# 2_Connectors.net
KiCad netlist of a schematic drawn in Altium Designer
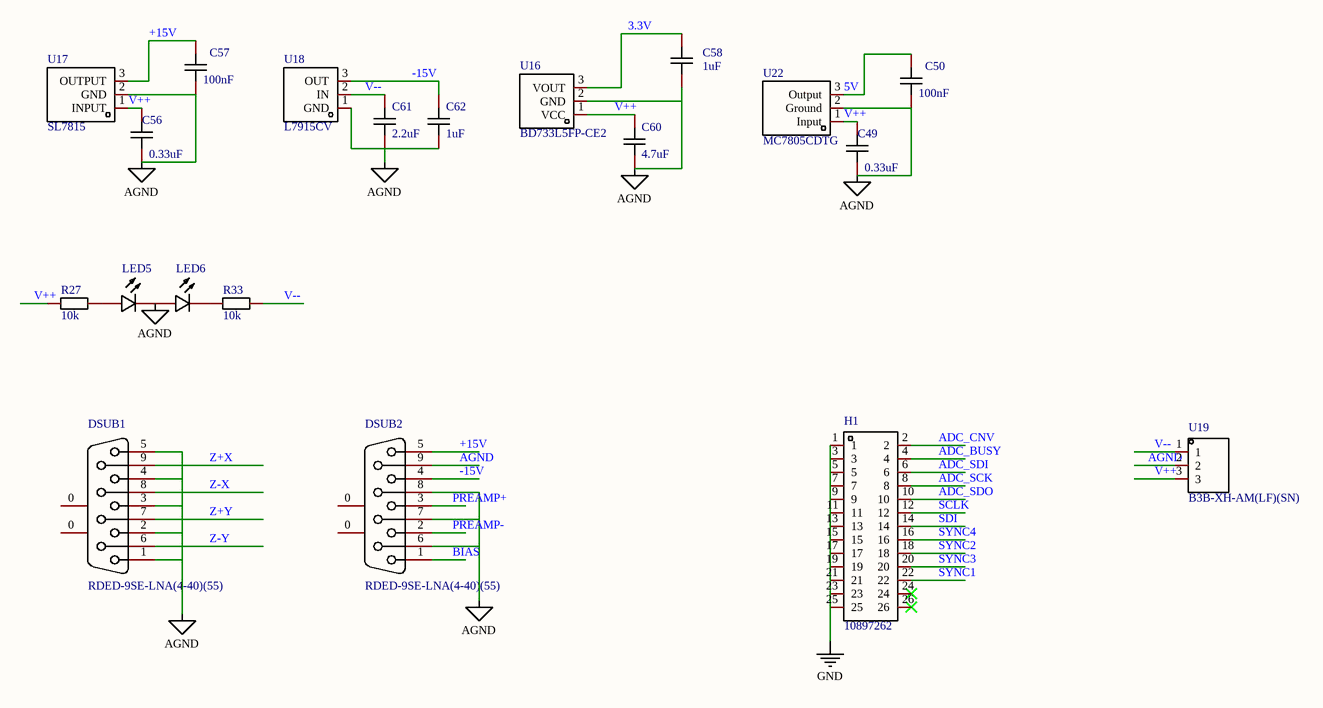
[diagram p0: 2_Connectors.schdoc]

(export (version "E")
  (design (tool "Eeschema 10.0.6"))
  (components
    (comp (ref "C49")
      (value "0.33uF")
      (fields (field (name "NAME") "0.33uF"))
      (libsource (lib "altium-import") (part "root_1_CAP_0603_"))
    )
    (comp (ref "C50")
      (value "100nF")
      (fields (field (name "NAME") "100nF"))
      (libsource (lib "altium-import") (part "root_3_CAP_0603_"))
    )
    (comp (ref "C56")
      (value "0.33uF")
      (fields (field (name "NAME") "0.33uF"))
      (libsource (lib "altium-import") (part "root_1_CAP_0603_"))
    )
    (comp (ref "C57")
      (value "100nF")
      (fields (field (name "NAME") "100nF"))
      (libsource (lib "altium-import") (part "root_3_CAP_0603_"))
    )
    (comp (ref "C58")
      (value "1uF")
      (fields (field (name "NAME") "1uF"))
      (libsource (lib "altium-import") (part "root_3_CAP_0603_"))
    )
    (comp (ref "C60")
      (value "4.7uF")
      (fields (field (name "NAME") "4.7uF"))
      (libsource (lib "altium-import") (part "root_1_CAP_0603_"))
    )
    (comp (ref "C61")
      (value "2.2uF")
      (fields (field (name "NAME") "2.2uF"))
      (libsource (lib "altium-import") (part "root_1_CAP_0603_"))
    )
    (comp (ref "C62")
      (value "1uF")
      (fields (field (name "NAME") "1uF"))
      (libsource (lib "altium-import") (part "root_3_CAP_0603_"))
    )
    (comp (ref "DSUB1")
      (value "RDED-9SE-LNA(4-40)(55)")
      (fields (field (name "NAME") "RDED-9SE-LNA(4-40)(55)") (field (name "MANUFACTURER") "HRS(广濑)"))
      (libsource (lib "altium-import") (part "root_0_RDED-9SE-LNA(4-40)(55)_"))
    )
    (comp (ref "DSUB2")
      (value "RDED-9SE-LNA(4-40)(55)")
      (fields (field (name "NAME") "RDED-9SE-LNA(4-40)(55)") (field (name "MANUFACTURER") "HRS(广濑)"))
      (libsource (lib "altium-import") (part "root_0_RDED-9SE-LNA(4-40)(55)_"))
    )
    (comp (ref "H1")
      (value "10897262")
      (fields (field (name "NAME") "10897262") (field (name "MANUFACTURER") "MOLEX"))
      (libsource (lib "altium-import") (part "root_0_10897262_"))
    )
    (comp (ref "LED5")
      (value "19-217/R6C-AL1M2VY/3T")
      (fields (field (name "MANUFACTURER") "EVERLIGHT(台湾亿光)"))
      (libsource (lib "altium-import") (part "root_0_19-217/R6C-AL1M2VY/3T_"))
    )
    (comp (ref "LED6")
      (value "19-217/R6C-AL1M2VY/3T")
      (fields (field (name "MANUFACTURER") "EVERLIGHT(台湾亿光)"))
      (libsource (lib "altium-import") (part "root_0_19-217/R6C-AL1M2VY/3T_"))
    )
    (comp (ref "R27")
      (value "10k")
      (description "电阻类型:厚膜电阻;阻值:10k;精度:±1%;功率:1/10W;温度系数:±100ppm/;最大工作电压:75V;工作温度范围:-55~+155;")
      (fields
        (field (name "MANUFACTURER") "UNI-ROYAL(厚声)")
        (field (name "MANUFACTURER PART") "0603WAF1002T5E")
      )
      (libsource (lib "altium-import") (part "root_0_0603WAF1002T5E_"))
    )
    (comp (ref "R33")
      (value "10k")
      (description "电阻类型:厚膜电阻;阻值:10k;精度:±1%;功率:1/10W;温度系数:±100ppm/;最大工作电压:75V;工作温度范围:-55~+155;")
      (fields
        (field (name "MANUFACTURER") "UNI-ROYAL(厚声)")
        (field (name "MANUFACTURER PART") "0603WAF1002T5E")
      )
      (libsource (lib "altium-import") (part "root_0_0603WAF1002T5E_"))
    )
    (comp (ref "U16")
      (value "BD733L5FP-CE2")
      (fields (field (name "NAME") "BD733L5FP-CE2") (field (name "MANUFACTURER") "ROHM(罗姆)"))
      (libsource (lib "altium-import") (part "root_2_BD733L5FP-CE2_"))
    )
    (comp (ref "U17")
      (value "SL7815")
      (fields (field (name "NAME") "SL7815") (field (name "MANUFACTURER") "Slkor(萨科微)"))
      (libsource (lib "altium-import") (part "root_2_SL7815_"))
    )
    (comp (ref "U18")
      (value "L7915CV")
      (fields (field (name "NAME") "L7915CV") (field (name "MANUFACTURER") "ST(意法半导体)"))
      (libsource (lib "altium-import") (part "root_2_L7915CV_"))
    )
    (comp (ref "U19")
      (value "B3B-XH-AM(LF)(SN)")
      (fields (field (name "NAME") "B3B-XH-AM(LF)(SN)") (field (name "MANUFACTURER") "JST"))
      (libsource (lib "altium-import") (part "root_0_B3B-XH-AM(LF)(SN)_"))
    )
    (comp (ref "U22")
      (value "MC7805CDTG")
      (fields (field (name "NAME") "MC7805CDTG") (field (name "MANUFACTURER") "onsemi(安森美)"))
      (libsource (lib "altium-import") (part "root_2_MC7805CDTG_"))
    )
  )
  (nets
    (net (code "1") (name "/+15V") (class "Default")
      (node (ref "C57") (pin "2") (pinfunction "2_2") (pintype "passive"))
      (node (ref "DSUB2") (pin "5") (pinfunction "5_5") (pintype "passive"))
      (node (ref "U17") (pin "3") (pinfunction "OUTPUT_3") (pintype "passive"))
    )
    (net (code "2") (name "/-15V") (class "Default")
      (node (ref "C62") (pin "2") (pinfunction "2_2") (pintype "passive"))
      (node (ref "DSUB2") (pin "4") (pinfunction "4_4") (pintype "passive"))
      (node (ref "U18") (pin "3") (pinfunction "OUT_3") (pintype "passive"))
    )
    (net (code "3") (name "/3.3V") (class "Default")
      (node (ref "C58") (pin "2") (pinfunction "2_2") (pintype "passive"))
      (node (ref "U16") (pin "3") (pinfunction "VOUT_3") (pintype "passive"))
    )
    (net (code "4") (name "/5V") (class "Default")
      (node (ref "C50") (pin "2") (pinfunction "2_2") (pintype "passive"))
      (node (ref "U22") (pin "3") (pinfunction "Output_3") (pintype "passive"))
    )
    (net (code "5") (name "/ADC_BUSY") (class "Default")
      (node (ref "H1") (pin "4") (pinfunction "4_4") (pintype "passive"))
    )
    (net (code "6") (name "/ADC_CNV") (class "Default")
      (node (ref "H1") (pin "2") (pinfunction "2_2") (pintype "passive"))
    )
    (net (code "7") (name "/ADC_SCK") (class "Default")
      (node (ref "H1") (pin "8") (pinfunction "8_8") (pintype "passive"))
    )
    (net (code "8") (name "/ADC_SDI") (class "Default")
      (node (ref "H1") (pin "6") (pinfunction "6_6") (pintype "passive"))
    )
    (net (code "9") (name "/ADC_SDO") (class "Default")
      (node (ref "H1") (pin "10") (pinfunction "10_10") (pintype "passive"))
    )
    (net (code "10") (name "/BIAS") (class "Default")
      (node (ref "DSUB2") (pin "1") (pinfunction "1_1") (pintype "passive"))
    )
    (net (code "11") (name "/PREAMP+") (class "Default")
      (node (ref "DSUB2") (pin "3") (pinfunction "3_3") (pintype "passive"))
    )
    (net (code "12") (name "/PREAMP-") (class "Default")
      (node (ref "DSUB2") (pin "2") (pinfunction "2_2") (pintype "passive"))
    )
    (net (code "13") (name "/SCLK") (class "Default")
      (node (ref "H1") (pin "12") (pinfunction "12_12") (pintype "passive"))
    )
    (net (code "14") (name "/SDI") (class "Default")
      (node (ref "H1") (pin "14") (pinfunction "14_14") (pintype "passive"))
    )
    (net (code "15") (name "/SYNC1") (class "Default")
      (node (ref "H1") (pin "22") (pinfunction "22_22") (pintype "passive"))
    )
    (net (code "16") (name "/SYNC2") (class "Default")
      (node (ref "H1") (pin "18") (pinfunction "18_18") (pintype "passive"))
    )
    (net (code "17") (name "/SYNC3") (class "Default")
      (node (ref "H1") (pin "20") (pinfunction "20_20") (pintype "passive"))
    )
    (net (code "18") (name "/SYNC4") (class "Default")
      (node (ref "H1") (pin "16") (pinfunction "16_16") (pintype "passive"))
    )
    (net (code "19") (name "/V++") (class "Default")
      (node (ref "C49") (pin "1") (pinfunction "1_1") (pintype "passive"))
      (node (ref "C56") (pin "1") (pinfunction "1_1") (pintype "passive"))
      (node (ref "C60") (pin "1") (pinfunction "1_1") (pintype "passive"))
      (node (ref "R27") (pin "1") (pinfunction "1_1") (pintype "passive"))
      (node (ref "U16") (pin "1") (pinfunction "VCC_1") (pintype "passive"))
      (node (ref "U17") (pin "1") (pinfunction "INPUT_1") (pintype "passive"))
      (node (ref "U19") (pin "3") (pinfunction "3_3") (pintype "passive"))
      (node (ref "U22") (pin "1") (pinfunction "Input_1") (pintype "passive"))
    )
    (net (code "20") (name "/V--") (class "Default")
      (node (ref "C61") (pin "1") (pinfunction "1_1") (pintype "passive"))
      (node (ref "R33") (pin "2") (pinfunction "2_2") (pintype "passive"))
      (node (ref "U18") (pin "2") (pinfunction "IN_2") (pintype "passive"))
      (node (ref "U19") (pin "1") (pinfunction "1_1") (pintype "passive"))
    )
    (net (code "21") (name "/Z+X") (class "Default")
      (node (ref "DSUB1") (pin "9") (pinfunction "9_9") (pintype "passive"))
    )
    (net (code "22") (name "/Z+Y") (class "Default")
      (node (ref "DSUB1") (pin "7") (pinfunction "7_7") (pintype "passive"))
    )
    (net (code "23") (name "/Z-X") (class "Default")
      (node (ref "DSUB1") (pin "8") (pinfunction "8_8") (pintype "passive"))
    )
    (net (code "24") (name "/Z-Y") (class "Default")
      (node (ref "DSUB1") (pin "6") (pinfunction "6_6") (pintype "passive"))
    )
    (net (code "25") (name "AGND") (class "Default")
      (node (ref "C49") (pin "2") (pinfunction "2_2") (pintype "passive"))
      (node (ref "C50") (pin "1") (pinfunction "1_1") (pintype "passive"))
      (node (ref "C56") (pin "2") (pinfunction "2_2") (pintype "passive"))
      (node (ref "C57") (pin "1") (pinfunction "1_1") (pintype "passive"))
      (node (ref "C58") (pin "1") (pinfunction "1_1") (pintype "passive"))
      (node (ref "C60") (pin "2") (pinfunction "2_2") (pintype "passive"))
      (node (ref "C61") (pin "2") (pinfunction "2_2") (pintype "passive"))
      (node (ref "C62") (pin "1") (pinfunction "1_1") (pintype "passive"))
      (node (ref "DSUB1") (pin "1") (pinfunction "1_1") (pintype "passive"))
      (node (ref "DSUB1") (pin "2") (pinfunction "2_2") (pintype "passive"))
      (node (ref "DSUB1") (pin "3") (pinfunction "3_3") (pintype "passive"))
      (node (ref "DSUB1") (pin "4") (pinfunction "4_4") (pintype "passive"))
      (node (ref "DSUB1") (pin "5") (pinfunction "5_5") (pintype "passive"))
      (node (ref "DSUB2") (pin "6") (pinfunction "6_6") (pintype "passive"))
      (node (ref "DSUB2") (pin "7") (pinfunction "7_7") (pintype "passive"))
      (node (ref "DSUB2") (pin "8") (pinfunction "8_8") (pintype "passive"))
      (node (ref "DSUB2") (pin "9") (pinfunction "9_9") (pintype "passive"))
      (node (ref "LED5") (pin "2") (pinfunction "C_2") (pintype "passive"))
      (node (ref "LED6") (pin "1") (pinfunction "A_1") (pintype "passive"))
      (node (ref "U16") (pin "2") (pinfunction "GND_2") (pintype "passive"))
      (node (ref "U17") (pin "2") (pinfunction "GND_2") (pintype "passive"))
      (node (ref "U18") (pin "1") (pinfunction "GND_1") (pintype "passive"))
      (node (ref "U19") (pin "2") (pinfunction "2_2") (pintype "passive"))
      (node (ref "U22") (pin "2") (pinfunction "Ground_2") (pintype "passive"))
    )
    (net (code "26") (name "GND") (class "Default")
      (node (ref "H1") (pin "1") (pinfunction "1_1") (pintype "passive"))
      (node (ref "H1") (pin "11") (pinfunction "11_11") (pintype "passive"))
      (node (ref "H1") (pin "13") (pinfunction "13_13") (pintype "passive"))
      (node (ref "H1") (pin "15") (pinfunction "15_15") (pintype "passive"))
      (node (ref "H1") (pin "17") (pinfunction "17_17") (pintype "passive"))
      (node (ref "H1") (pin "19") (pinfunction "19_19") (pintype "passive"))
      (node (ref "H1") (pin "21") (pinfunction "21_21") (pintype "passive"))
      (node (ref "H1") (pin "23") (pinfunction "23_23") (pintype "passive"))
      (node (ref "H1") (pin "25") (pinfunction "25_25") (pintype "passive"))
      (node (ref "H1") (pin "3") (pinfunction "3_3") (pintype "passive"))
      (node (ref "H1") (pin "5") (pinfunction "5_5") (pintype "passive"))
      (node (ref "H1") (pin "7") (pinfunction "7_7") (pintype "passive"))
      (node (ref "H1") (pin "9") (pinfunction "9_9") (pintype "passive"))
    )
    (net (code "27") (name "Net-(LED5-A)") (class "Default")
      (node (ref "LED5") (pin "1") (pinfunction "A_1") (pintype "passive"))
      (node (ref "R27") (pin "2") (pinfunction "2_2") (pintype "passive"))
    )
    (net (code "28") (name "Net-(LED6-C)") (class "Default")
      (node (ref "LED6") (pin "2") (pinfunction "C_2") (pintype "passive"))
      (node (ref "R33") (pin "1") (pinfunction "1_1") (pintype "passive"))
    )
    (net (code "29") (name "unconnected-(DSUB1-Pad0)") (class "Default")
      (node (ref "DSUB1") (pin "0") (pinfunction "0_0") (pintype "passive"))
    )
    (net (code "30") (name "unconnected-(DSUB1-Pad0)_1") (class "Default")
      (node (ref "DSUB1") (pin "0") (pinfunction "0_0") (pintype "passive"))
    )
    (net (code "31") (name "unconnected-(DSUB2-Pad0)") (class "Default")
      (node (ref "DSUB2") (pin "0") (pinfunction "0_0") (pintype "passive"))
    )
    (net (code "32") (name "unconnected-(DSUB2-Pad0)_1") (class "Default")
      (node (ref "DSUB2") (pin "0") (pinfunction "0_0") (pintype "passive"))
    )
    (net (code "33") (name "unconnected-(H1-Pad24)") (class "Default")
      (node (ref "H1") (pin "24") (pinfunction "24_24") (pintype "passive+no_connect"))
    )
    (net (code "34") (name "unconnected-(H1-Pad26)") (class "Default")
      (node (ref "H1") (pin "26") (pinfunction "26_26") (pintype "passive+no_connect"))
    )
  )
)
